# Ethernet_PHY.net
KiCad netlist of a schematic drawn in Altium Designer
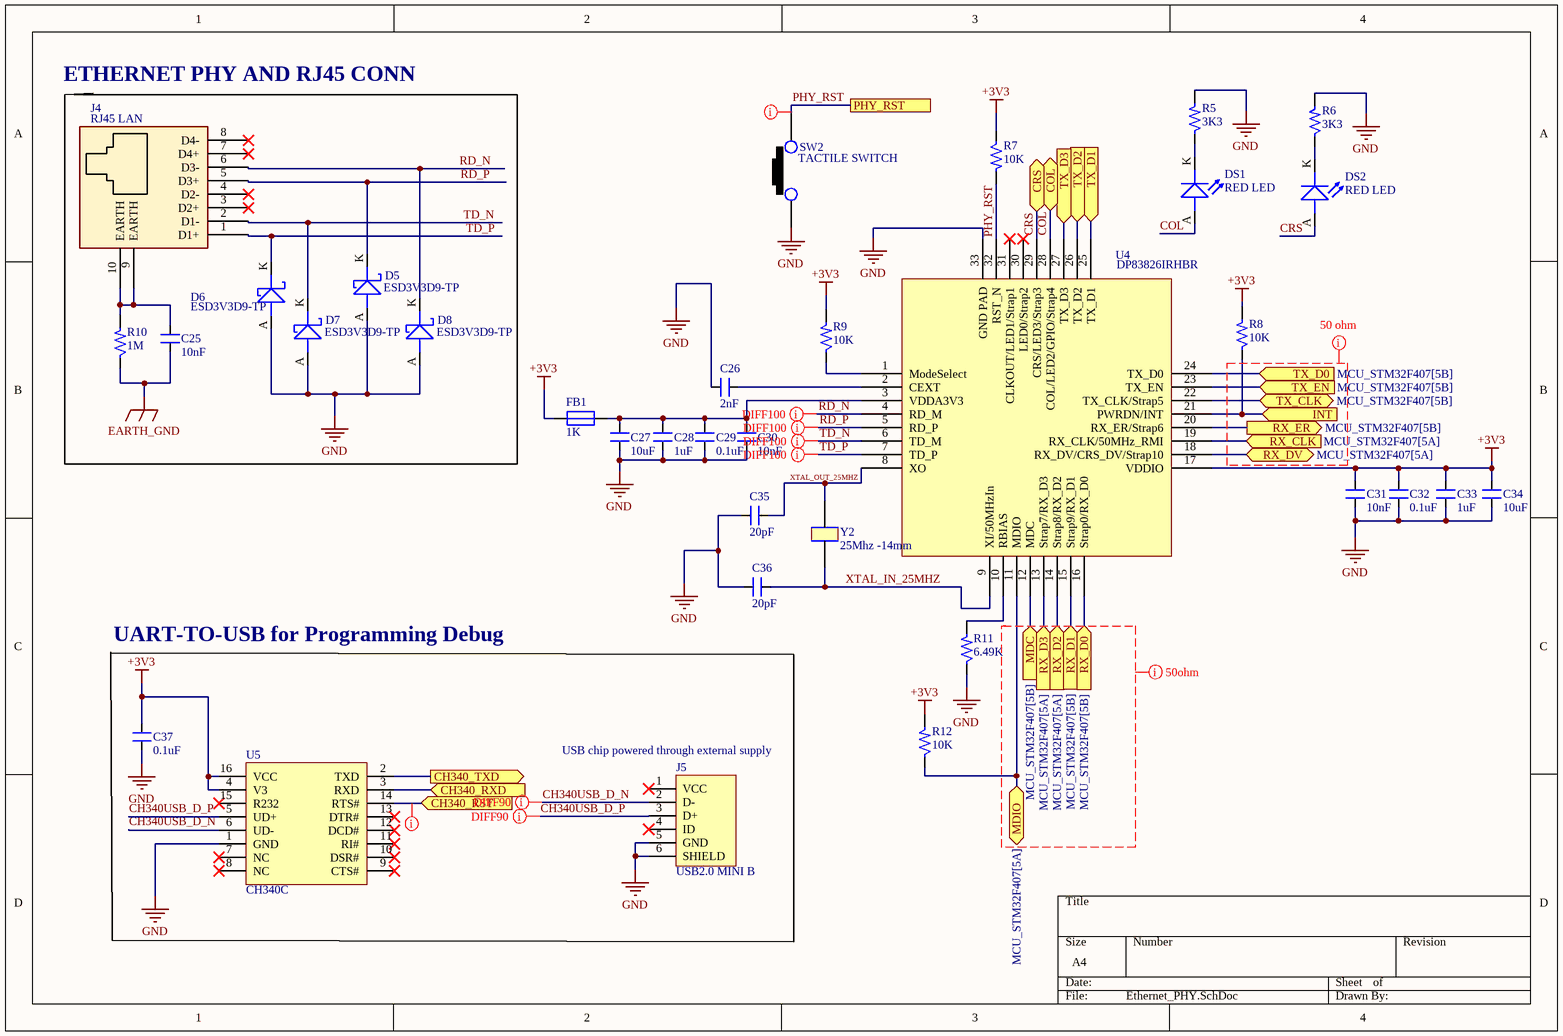
[diagram p0: Ethernet_PHY.SchDoc]

(export (version "E")
  (design (tool "Eeschema 10.0.6"))
  (components
    (comp (ref "C25")
      (value "10nF")
      (footprint "CAP_P196_102X287_H332_RAD_TH")
      (description "10000pF ±10% 1000V (1kV) Ceramic Capacitor X7R Radial")
      (fields
        (field (name "MANUFACTURER") "Yageo")
        (field (name "MANUFACTURER PART NUMBER") "RDER73A103K2K1H03B")
      )
      (libsource (lib "STM32F407_Board") (part "CAP_10nF-1KV-10%-RAD-TH"))
    )
    (comp (ref "C26")
      (value "2nF")
      (footprint "CAP_0805")
      (description "2000pF ±10% 50V Ceramic Capacitor X7R 0805 (2012 Metric)")
      (fields
        (field (name "MANUFACTURER") "Samsung Electro-Mechanics")
        (field (name "MANUFACTURER PART NUMBER") "CL21B202KBANNNC")
      )
      (libsource (lib "STM32F407_Board") (part "CAP_2nF-50V-10%-0805"))
    )
    (comp (ref "C27")
      (value "10uF")
      (footprint "CAP_1206")
      (description "10µF ±10% 50V Ceramic Capacitor X7R 1206 (3216 Metric)")
      (fields
        (field (name "MANUFACTURER") "KEMET")
        (field (name "MANUFACTURER PART NUMBER") "CL31B106KBHNNNE")
      )
      (libsource (lib "STM32F407_Board") (part "CAP_10uF-50V-10%-1206"))
    )
    (comp (ref "C28")
      (value "1uF")
      (footprint "CAP_0805")
      (description "1µF ±5% 50V Ceramic Capacitor X7R 0805 (2012 Metric)")
      (fields
        (field (name "MANUFACTURER") "Samsung")
        (field (name "MANUFACTURER PART NUMBER") "CC0805JKX7R9BB105")
      )
      (libsource (lib "STM32F407_Board") (part "CAP_1uF-50V-5%-0805"))
    )
    (comp (ref "C29")
      (value "0.1uF")
      (footprint "CAP_0805")
      (description "0.1µF ±10% 50V Ceramic Capacitor X7R 0805 (2012 Metric)")
      (fields
        (field (name "MANUFACTURER") "Samsung")
        (field (name "MANUFACTURER PART NUMBER") "CL21B104KBCNNNC")
      )
      (libsource (lib "STM32F407_Board") (part "CAP_0.1uF-50V-10%-0805"))
    )
    (comp (ref "C30")
      (value "10nF")
      (footprint "CAP_0805")
      (description "10000pF ±10% 50V Ceramic Capacitor X7R 0805 (2012 Metric)")
      (fields
        (field (name "MANUFACTURER") "Samsung")
        (field (name "MANUFACTURER PART NUMBER") "C0805C103K5RECAUTO")
      )
      (libsource (lib "STM32F407_Board") (part "CAP_10nF-50V-10%-0805"))
    )
    (comp (ref "C31")
      (value "10nF")
      (footprint "CAP_0805")
      (description "10000pF ±10% 50V Ceramic Capacitor X7R 0805 (2012 Metric)")
      (fields
        (field (name "MANUFACTURER") "Samsung")
        (field (name "MANUFACTURER PART NUMBER") "C0805C103K5RECAUTO")
      )
      (libsource (lib "STM32F407_Board") (part "CAP_10nF-50V-10%-0805"))
    )
    (comp (ref "C32")
      (value "0.1uF")
      (footprint "CAP_0805")
      (description "0.1µF ±10% 50V Ceramic Capacitor X7R 0805 (2012 Metric)")
      (fields
        (field (name "MANUFACTURER") "Samsung")
        (field (name "MANUFACTURER PART NUMBER") "CL21B104KBCNNNC")
      )
      (libsource (lib "STM32F407_Board") (part "CAP_0.1uF-50V-10%-0805"))
    )
    (comp (ref "C33")
      (value "1uF")
      (footprint "CAP_0805")
      (description "1µF ±5% 50V Ceramic Capacitor X7R 0805 (2012 Metric)")
      (fields
        (field (name "MANUFACTURER") "Samsung")
        (field (name "MANUFACTURER PART NUMBER") "CC0805JKX7R9BB105")
      )
      (libsource (lib "STM32F407_Board") (part "CAP_1uF-50V-5%-0805"))
    )
    (comp (ref "C34")
      (value "10uF")
      (footprint "CAP_1206")
      (description "10µF ±10% 50V Ceramic Capacitor X7R 1206 (3216 Metric)")
      (fields
        (field (name "MANUFACTURER") "KEMET")
        (field (name "MANUFACTURER PART NUMBER") "CL31B106KBHNNNE")
      )
      (libsource (lib "STM32F407_Board") (part "CAP_10uF-50V-10%-1206"))
    )
    (comp (ref "C35")
      (value "20pF")
      (footprint "CAP_0805")
      (description "±10% 50V Ceramic Capacitor C0G, NP0 0805 (2012 Metric)")
      (fields
        (field (name "MANUFACTURER") "AVX Corporation")
        (field (name "MANUFACTURER PART NUMBER") "08055A200KAT2A")
      )
      (libsource (lib "STM32F407_Board") (part "CAP_20pF-50V-10%-0805"))
    )
    (comp (ref "C36")
      (value "20pF")
      (footprint "CAP_0805")
      (description "±10% 50V Ceramic Capacitor C0G, NP0 0805 (2012 Metric)")
      (fields
        (field (name "MANUFACTURER") "AVX Corporation")
        (field (name "MANUFACTURER PART NUMBER") "08055A200KAT2A")
      )
      (libsource (lib "STM32F407_Board") (part "CAP_20pF-50V-10%-0805"))
    )
    (comp (ref "C37")
      (value "0.1uF")
      (footprint "CAP_0805")
      (description "0.1µF ±5% 50V Ceramic Capacitor X7R 0805 (2012 Metric)")
      (fields
        (field (name "MANUFACTURER") "AVX Corporation")
        (field (name "MANUFACTURER PART NUMBER") "08055C104JAT4A")
      )
      (libsource (lib "STM32F407_Board") (part "CAP_0.1uF-50V-5%-0805"))
    )
    (comp (ref "D5")
      (value "ESD3V3D9-TP")
      (footprint "DIO_SOD-923")
      (description "8.8V Clamp 5A (8/20µs) Ipp Tvs Diode Surface Mount SOD-923")
      (fields (field (name "MANUFACTURER") "Micro Commercial Co"))
      (libsource (lib "STM32F407_Board") (part "DIO-T_3.3V-8.8V-SOD923"))
    )
    (comp (ref "D6")
      (value "ESD3V3D9-TP")
      (footprint "DIO_SOD-923")
      (description "8.8V Clamp 5A (8/20µs) Ipp Tvs Diode Surface Mount SOD-923")
      (fields (field (name "MANUFACTURER") "Micro Commercial Co"))
      (libsource (lib "STM32F407_Board") (part "DIO-T_3.3V-8.8V-SOD923"))
    )
    (comp (ref "D7")
      (value "ESD3V3D9-TP")
      (footprint "DIO_SOD-923")
      (description "8.8V Clamp 5A (8/20µs) Ipp Tvs Diode Surface Mount SOD-923")
      (fields (field (name "MANUFACTURER") "Micro Commercial Co"))
      (libsource (lib "STM32F407_Board") (part "DIO-T_3.3V-8.8V-SOD923"))
    )
    (comp (ref "D8")
      (value "ESD3V3D9-TP")
      (footprint "DIO_SOD-923")
      (description "8.8V Clamp 5A (8/20µs) Ipp Tvs Diode Surface Mount SOD-923")
      (fields (field (name "MANUFACTURER") "Micro Commercial Co"))
      (libsource (lib "STM32F407_Board") (part "DIO-T_3.3V-8.8V-SOD923"))
    )
    (comp (ref "DS1")
      (value "RED LED")
      (footprint "LED_0805")
      (description "Red 631nm LED Indication - Discrete 2V 0805 (2012 Metric)")
      (fields
        (field (name "MANUFACTURER") "Vishay Lite-On")
        (field (name "MANUFACTURER PART NUMBER") "LTST-C171KRKT")
      )
      (libsource (lib "STM32F407_Board") (part "LED_RED-2V-20mA-0805"))
    )
    (comp (ref "DS2")
      (value "RED LED")
      (footprint "LED_0805")
      (description "Red 631nm LED Indication - Discrete 2V 0805 (2012 Metric)")
      (fields
        (field (name "MANUFACTURER") "Vishay Lite-On")
        (field (name "MANUFACTURER PART NUMBER") "LTST-C171KRKT")
      )
      (libsource (lib "STM32F407_Board") (part "LED_RED-2V-20mA-0805"))
    )
    (comp (ref "FB1")
      (value "1K")
      (footprint "IND_0805")
      (description "1 kOhms @ 100MHz 1 Power Line Ferrite Bead 0805 (2012 Metric) 1.6A")
      (fields
        (field (name "MANUFACTURER") "Laird")
        (field (name "MANUFACTURER PART NUMBER") "BLM21SP102SH1D")
      )
      (libsource (lib "STM32F407_Board") (part "FB_1K-100MHZ-1.6A-0805"))
    )
    (comp (ref "J4")
      (value "RJ45 LAN")
      (footprint "CON10_P106_RJ45_TH_ST")
      (description "8 Pins, 2 Row 2.54mm Pitch, right angle Connector, male")
      (fields
        (field (name "MANUFACTURER") "Assmann")
        (field (name "MANUFACTURER PART NUMBER") "A-2004-2-4-LPS-N-R")
      )
      (libsource (lib "STM32F407_Board") (part "CON-SKT-RJ_8C8P-RA-TH"))
    )
    (comp (ref "J5")
      (value "USB2.0 MINI B")
      (footprint "CON_690-005-299-043")
      (description "USB - mini B USB 2.0 Receptacle Connector 5 Position Surface Mount, Right Angle")
      (fields
        (field (name "MANUFACTURER") "EDAC")
        (field (name "MANUFACTURER PART NUMBER") "690-005-299-043")
      )
      (libsource (lib "STM32F407_Board") (part "CON_USB2.0-MINIB-SMD"))
    )
    (comp (ref "R5")
      (value "3K3")
      (footprint "RES_0603")
      (description "3.3 kOhms ±1% 0.1W, 1/10W Chip Resistor 0603 (1608 Metric) Automotive AEC-Q200 Thick Film")
      (fields (field (name "MANUFACTURER") "Wilson") (field (name "MANUFACTURER PART NUMBER") "WR06X3301FTL"))
      (libsource (lib "STM32F407_Board") (part "RES_3.3K-0.1W-1%-0603"))
    )
    (comp (ref "R6")
      (value "3K3")
      (footprint "RES_0603")
      (description "3.3 kOhms ±1% 0.1W, 1/10W Chip Resistor 0603 (1608 Metric) Automotive AEC-Q200 Thick Film")
      (fields (field (name "MANUFACTURER") "Wilson") (field (name "MANUFACTURER PART NUMBER") "WR06X3301FTL"))
      (libsource (lib "STM32F407_Board") (part "RES_3.3K-0.1W-1%-0603"))
    )
    (comp (ref "R7")
      (value "10K")
      (footprint "RES_0603")
      (description "10 kOhms ±1% 0.1W, 1/10W Chip Resistor 0603 (1608 Metric) Automotive AEC-Q200 Thick Film")
      (fields (field (name "MANUFACTURER") "Walsin") (field (name "MANUFACTURER PART NUMBER") "WR06X1002FTL"))
      (libsource (lib "STM32F407_Board") (part "RES_10K-0.1W-1%-0603"))
    )
    (comp (ref "R8")
      (value "10K")
      (footprint "RES_0603")
      (description "10 kOhms ±1% 0.1W, 1/10W Chip Resistor 0603 (1608 Metric) Automotive AEC-Q200 Thick Film")
      (fields (field (name "MANUFACTURER") "Walsin") (field (name "MANUFACTURER PART NUMBER") "WR06X1002FTL"))
      (libsource (lib "STM32F407_Board") (part "RES_10K-0.1W-1%-0603"))
    )
    (comp (ref "R9")
      (value "10K")
      (footprint "RES_0603")
      (description "10 kOhms ±1% 0.1W, 1/10W Chip Resistor 0603 (1608 Metric) Automotive AEC-Q200 Thick Film")
      (fields (field (name "MANUFACTURER") "Walsin") (field (name "MANUFACTURER PART NUMBER") "WR06X1002FTL"))
      (libsource (lib "STM32F407_Board") (part "RES_10K-0.1W-1%-0603"))
    )
    (comp (ref "R10")
      (value "1M")
      (footprint "RES_1206")
      (fields (field (name "MANUFACTURER") "Walsin") (field (name "MANUFACTURER PART NUMBER") "WR12X1004FTL"))
      (libsource (lib "STM32F407_Board") (part "RES_1M-0.25W-1%-1206"))
    )
    (comp (ref "R11")
      (value "6.49K")
      (footprint "RES_0805")
      (description "6.49 kOhms ±1% 0.125W, 1/8W Chip Resistor 0805 (2012 Metric) Moisture Resistant Thick Film")
      (fields
        (field (name "MANUFACTURER") "Stackpole Electronics")
        (field (name "MANUFACTURER PART NUMBER") "RC0805FR-076K49L")
      )
      (libsource (lib "STM32F407_Board") (part "RES_6.49K-0.125W-1%-0805"))
    )
    (comp (ref "R12")
      (value "10K")
      (footprint "RES_0603")
      (description "10 kOhms ±1% 0.1W, 1/10W Chip Resistor 0603 (1608 Metric) Automotive AEC-Q200 Thick Film")
      (fields (field (name "MANUFACTURER") "Walsin") (field (name "MANUFACTURER PART NUMBER") "WR06X1002FTL"))
      (libsource (lib "STM32F407_Board") (part "RES_10K-0.1W-1%-0603"))
    )
    (comp (ref "SW2")
      (value "TACTILE SWITCH")
      (footprint "SW_342_SMD")
      (description "Tactile Switch SPST-NO Top Actuated Surface Mount")
      (fields
        (field (name "MANUFACTURER") "ITT C&K")
        (field (name "MANUFACTURER PART NUMBER") "RS-282G05A3-SMRT")
      )
      (libsource (lib "STM32F407_Board") (part "SW1_RS-282G05A3-SMRT-SMD"))
    )
    (comp (ref "U4")
      (value "DP83826IRHBR")
      (footprint "VQFN32_19_218_23X9_SMD")
      (fields (field (name "MANUFACTURER") "Texas Instruments"))
      (libsource (lib "STM32F407_Board") (part "IC_DP83826IRHBR"))
    )
    (comp (ref "U5")
      (value "CH340C")
      (footprint "SOIC16_50_284_25X90_SMT")
      (description "USB Bridge, USB to UART USB 2.0 UART Interface")
      (fields (field (name "MANUFACTURER") "Olimex"))
      (libsource (lib "STM32F407_Board") (part "IC_CH340C"))
    )
    (comp (ref "Y2")
      (value "25Mhz -14mm")
      (footprint "XTAL_314_240X47_SMD")
      (description "25MHz ±30ppm Crystal 20pF 30 Ohms HC-49/US")
      (fields
        (field (name "MANUFACTURER") "Abracon")
        (field (name "MANUFACTURER PART NUMBER") "FOXSDLF/250F-20")
      )
      (libsource (lib "STM32F407_Board") (part "XTAL_25Mhz-FOXSDLF/250F-20"))
    )
  )
  (nets
    (net (code "1") (name "+3V3") (class "Default")
      (node (ref "C31") (pin "2") (pinfunction "2_2") (pintype "passive"))
      (node (ref "C32") (pin "2") (pinfunction "2_2") (pintype "passive"))
      (node (ref "C33") (pin "2") (pinfunction "2_2") (pintype "passive"))
      (node (ref "C34") (pin "2") (pinfunction "2_2") (pintype "passive"))
      (node (ref "C37") (pin "2") (pinfunction "2_2") (pintype "passive"))
      (node (ref "FB1") (pin "1") (pinfunction "1_1") (pintype "passive"))
      (node (ref "R12") (pin "2") (pinfunction "2_2") (pintype "passive"))
      (node (ref "R7") (pin "1") (pinfunction "1_1") (pintype "passive"))
      (node (ref "R8") (pin "2") (pinfunction "2_2") (pintype "passive"))
      (node (ref "R9") (pin "2") (pinfunction "2_2") (pintype "passive"))
      (node (ref "U4") (pin "17") (pinfunction "VDDIO_17") (pintype "passive"))
      (node (ref "U5") (pin "16") (pinfunction "VCC_16") (pintype "passive"))
      (node (ref "U5") (pin "4") (pinfunction "V3_4") (pintype "passive"))
    )
    (net (code "2") (name "/CH340USB_D_N") (class "Default")
      (node (ref "J5") (pin "2") (pinfunction "D-_2") (pintype "passive"))
      (node (ref "U5") (pin "6") (pinfunction "UD-_6") (pintype "passive"))
    )
    (net (code "3") (name "/CH340USB_D_P") (class "Default")
      (node (ref "J5") (pin "3") (pinfunction "D+_3") (pintype "passive"))
      (node (ref "U5") (pin "5") (pinfunction "UD+_5") (pintype "passive"))
    )
    (net (code "4") (name "/CH340_RST") (class "Default")
      (node (ref "U5") (pin "14") (pinfunction "RTS#_14") (pintype "passive"))
    )
    (net (code "5") (name "/CH340_RXD") (class "Default")
      (node (ref "U5") (pin "3") (pinfunction "RXD_3") (pintype "passive"))
    )
    (net (code "6") (name "/CH340_TXD") (class "Default")
      (node (ref "U5") (pin "2") (pinfunction "TXD_2") (pintype "passive"))
    )
    (net (code "7") (name "/COL") (class "Default")
      (node (ref "DS1") (pin "A") (pinfunction "ANODE_A") (pintype "passive"))
      (node (ref "U4") (pin "28") (pinfunction "COL/LED2/GPIO/Strap4_28") (pintype "passive"))
    )
    (net (code "8") (name "/CRS") (class "Default")
      (node (ref "DS2") (pin "A") (pinfunction "ANODE_A") (pintype "passive"))
      (node (ref "U4") (pin "29") (pinfunction "CRS/LED3/Strap3_29") (pintype "passive"))
    )
    (net (code "9") (name "/INT") (class "Default")
      (node (ref "R8") (pin "1") (pinfunction "1_1") (pintype "passive"))
      (node (ref "U4") (pin "21") (pinfunction "PWRDN/INT_21") (pintype "passive"))
    )
    (net (code "10") (name "/MDC") (class "Default")
      (node (ref "U4") (pin "12") (pinfunction "MDC_12") (pintype "passive"))
    )
    (net (code "11") (name "/MDIO") (class "Default")
      (node (ref "R12") (pin "1") (pinfunction "1_1") (pintype "passive"))
      (node (ref "U4") (pin "11") (pinfunction "MDIO_11") (pintype "passive"))
    )
    (net (code "12") (name "/PHY_RST") (class "Default")
      (node (ref "R7") (pin "2") (pinfunction "2_2") (pintype "passive"))
      (node (ref "SW2") (pin "2") (pinfunction "2_2") (pintype "passive"))
      (node (ref "U4") (pin "32") (pinfunction "RST_N_32") (pintype "passive"))
    )
    (net (code "13") (name "/RD_N") (class "Default")
      (node (ref "D8") (pin "K") (pinfunction "K_K") (pintype "passive"))
      (node (ref "J4") (pin "6") (pinfunction "D3-_6") (pintype "passive"))
      (node (ref "U4") (pin "4") (pinfunction "RD_M_4") (pintype "passive"))
    )
    (net (code "14") (name "/RD_P") (class "Default")
      (node (ref "D5") (pin "K") (pinfunction "K_K") (pintype "passive"))
      (node (ref "J4") (pin "5") (pinfunction "D3+_5") (pintype "passive"))
      (node (ref "U4") (pin "5") (pinfunction "RD_P_5") (pintype "passive"))
    )
    (net (code "15") (name "/RX_CLK") (class "Default")
      (node (ref "U4") (pin "19") (pinfunction "RX_CLK/50MHz_RMI_19") (pintype "passive"))
    )
    (net (code "16") (name "/RX_D0") (class "Default")
      (node (ref "U4") (pin "16") (pinfunction "Strap0/RX_D0_16") (pintype "passive"))
    )
    (net (code "17") (name "/RX_D1") (class "Default")
      (node (ref "U4") (pin "15") (pinfunction "Strap9/RX_D1_15") (pintype "passive"))
    )
    (net (code "18") (name "/RX_D2") (class "Default")
      (node (ref "U4") (pin "14") (pinfunction "Strap8/RX_D2_14") (pintype "passive"))
    )
    (net (code "19") (name "/RX_D3") (class "Default")
      (node (ref "U4") (pin "13") (pinfunction "Strap7/RX_D3_13") (pintype "passive"))
    )
    (net (code "20") (name "/RX_DV") (class "Default")
      (node (ref "U4") (pin "18") (pinfunction "RX_DV/CRS_DV/Strap10_18") (pintype "passive"))
    )
    (net (code "21") (name "/RX_ER") (class "Default")
      (node (ref "U4") (pin "20") (pinfunction "RX_ER/Strap6_20") (pintype "passive"))
    )
    (net (code "22") (name "/TD_N") (class "Default")
      (node (ref "D7") (pin "K") (pinfunction "K_K") (pintype "passive"))
      (node (ref "J4") (pin "2") (pinfunction "D1-_2") (pintype "passive"))
      (node (ref "U4") (pin "6") (pinfunction "TD_M_6") (pintype "passive"))
    )
    (net (code "23") (name "/TD_P") (class "Default")
      (node (ref "D6") (pin "K") (pinfunction "K_K") (pintype "passive"))
      (node (ref "J4") (pin "1") (pinfunction "D1+_1") (pintype "passive"))
      (node (ref "U4") (pin "7") (pinfunction "TD_P_7") (pintype "passive"))
    )
    (net (code "24") (name "/TX_CLK") (class "Default")
      (node (ref "U4") (pin "22") (pinfunction "TX_CLK/Strap5_22") (pintype "passive"))
    )
    (net (code "25") (name "/TX_D0") (class "Default")
      (node (ref "U4") (pin "24") (pinfunction "TX_D0_24") (pintype "passive"))
    )
    (net (code "26") (name "/TX_D1") (class "Default")
      (node (ref "U4") (pin "25") (pinfunction "TX_D1_25") (pintype "passive"))
    )
    (net (code "27") (name "/TX_D2") (class "Default")
      (node (ref "U4") (pin "26") (pinfunction "TX_D2_26") (pintype "passive"))
    )
    (net (code "28") (name "/TX_D3") (class "Default")
      (node (ref "U4") (pin "27") (pinfunction "TX_D3_27") (pintype "passive"))
    )
    (net (code "29") (name "/TX_EN") (class "Default")
      (node (ref "U4") (pin "23") (pinfunction "TX_EN_23") (pintype "passive"))
    )
    (net (code "30") (name "/XTAL_IN_25MHZ") (class "Default")
      (node (ref "C36") (pin "2") (pinfunction "2_2") (pintype "passive"))
      (node (ref "U4") (pin "9") (pinfunction "XI/50MHzIn_9") (pintype "passive"))
      (node (ref "Y2") (pin "2") (pinfunction "2_2") (pintype "passive"))
    )
    (net (code "31") (name "/XTAL_OUT_25MHZ") (class "Default")
      (node (ref "C35") (pin "2") (pinfunction "2_2") (pintype "passive"))
      (node (ref "U4") (pin "8") (pinfunction "XO_8") (pintype "passive"))
      (node (ref "Y2") (pin "1") (pinfunction "1_1") (pintype "passive"))
    )
    (net (code "32") (name "EARTH_GND") (class "Default")
      (node (ref "C25") (pin "1") (pinfunction "1_1") (pintype "passive"))
      (node (ref "R10") (pin "1") (pinfunction "1_1") (pintype "passive"))
    )
    (net (code "33") (name "GND") (class "Default")
      (node (ref "C26") (pin "2") (pinfunction "2_2") (pintype "passive"))
      (node (ref "C27") (pin "1") (pinfunction "1_1") (pintype "passive"))
      (node (ref "C28") (pin "1") (pinfunction "1_1") (pintype "passive"))
      (node (ref "C29") (pin "1") (pinfunction "1_1") (pintype "passive"))
      (node (ref "C30") (pin "1") (pinfunction "1_1") (pintype "passive"))
      (node (ref "C31") (pin "1") (pinfunction "1_1") (pintype "passive"))
      (node (ref "C32") (pin "1") (pinfunction "1_1") (pintype "passive"))
      (node (ref "C33") (pin "1") (pinfunction "1_1") (pintype "passive"))
      (node (ref "C34") (pin "1") (pinfunction "1_1") (pintype "passive"))
      (node (ref "C35") (pin "1") (pinfunction "1_1") (pintype "passive"))
      (node (ref "C36") (pin "1") (pinfunction "1_1") (pintype "passive"))
      (node (ref "C37") (pin "1") (pinfunction "1_1") (pintype "passive"))
      (node (ref "D5") (pin "A") (pinfunction "A_A") (pintype "passive"))
      (node (ref "D6") (pin "A") (pinfunction "A_A") (pintype "passive"))
      (node (ref "D7") (pin "A") (pinfunction "A_A") (pintype "passive"))
      (node (ref "D8") (pin "A") (pinfunction "A_A") (pintype "passive"))
      (node (ref "J5") (pin "5") (pinfunction "GND_5") (pintype "passive"))
      (node (ref "J5") (pin "6") (pinfunction "SHIELD_6") (pintype "passive"))
      (node (ref "R11") (pin "1") (pinfunction "1_1") (pintype "passive"))
      (node (ref "R5") (pin "2") (pinfunction "2_2") (pintype "passive"))
      (node (ref "R6") (pin "2") (pinfunction "2_2") (pintype "passive"))
      (node (ref "SW2") (pin "1") (pinfunction "1_1") (pintype "passive"))
      (node (ref "U4") (pin "33") (pinfunction "GND_PAD_33") (pintype "passive"))
      (node (ref "U5") (pin "1") (pinfunction "GND_1") (pintype "passive"))
    )
    (net (code "34") (name "Net-(C25-Pad2)") (class "Default")
      (node (ref "C25") (pin "2") (pinfunction "2_2") (pintype "passive"))
      (node (ref "J4") (pin "10") (pinfunction "EARTH_10") (pintype "passive"))
      (node (ref "J4") (pin "9") (pinfunction "EARTH_9") (pintype "passive"))
      (node (ref "R10") (pin "2") (pinfunction "2_2") (pintype "passive"))
    )
    (net (code "35") (name "Net-(DS1-CATHODE)") (class "Default")
      (node (ref "DS1") (pin "K") (pinfunction "CATHODE_K") (pintype "passive"))
      (node (ref "R5") (pin "1") (pinfunction "1_1") (pintype "passive"))
    )
    (net (code "36") (name "Net-(DS2-CATHODE)") (class "Default")
      (node (ref "DS2") (pin "K") (pinfunction "CATHODE_K") (pintype "passive"))
      (node (ref "R6") (pin "1") (pinfunction "1_1") (pintype "passive"))
    )
    (net (code "37") (name "Net-(U4-CEXT)") (class "Default")
      (node (ref "C26") (pin "1") (pinfunction "1_1") (pintype "passive"))
      (node (ref "U4") (pin "2") (pinfunction "CEXT_2") (pintype "passive"))
    )
    (net (code "38") (name "Net-(U4-ModeSelect)") (class "Default")
      (node (ref "R9") (pin "1") (pinfunction "1_1") (pintype "passive"))
      (node (ref "U4") (pin "1") (pinfunction "ModeSelect_1") (pintype "passive"))
    )
    (net (code "39") (name "Net-(U4-RBIAS)") (class "Default")
      (node (ref "R11") (pin "2") (pinfunction "2_2") (pintype "passive"))
      (node (ref "U4") (pin "10") (pinfunction "RBIAS_10") (pintype "passive"))
    )
    (net (code "40") (name "Net-(U4-VDDA3V3)") (class "Default")
      (node (ref "C27") (pin "2") (pinfunction "2_2") (pintype "passive"))
      (node (ref "C28") (pin "2") (pinfunction "2_2") (pintype "passive"))
      (node (ref "C29") (pin "2") (pinfunction "2_2") (pintype "passive"))
      (node (ref "C30") (pin "2") (pinfunction "2_2") (pintype "passive"))
      (node (ref "FB1") (pin "2") (pinfunction "2_2") (pintype "passive"))
      (node (ref "U4") (pin "3") (pinfunction "VDDA3V3_3") (pintype "passive"))
    )
    (net (code "41") (name "unconnected-(J4-D2+-Pad3)") (class "Default")
      (node (ref "J4") (pin "3") (pinfunction "D2+_3") (pintype "passive+no_connect"))
    )
    (net (code "42") (name "unconnected-(J4-D2--Pad4)") (class "Default")
      (node (ref "J4") (pin "4") (pinfunction "D2-_4") (pintype "passive+no_connect"))
    )
    (net (code "43") (name "unconnected-(J4-D4+-Pad7)") (class "Default")
      (node (ref "J4") (pin "7") (pinfunction "D4+_7") (pintype "passive+no_connect"))
    )
    (net (code "44") (name "unconnected-(J4-D4--Pad8)") (class "Default")
      (node (ref "J4") (pin "8") (pinfunction "D4-_8") (pintype "passive+no_connect"))
    )
    (net (code "45") (name "unconnected-(J5-ID-Pad4)") (class "Default")
      (node (ref "J5") (pin "4") (pinfunction "ID_4") (pintype "passive+no_connect"))
    )
    (net (code "46") (name "unconnected-(J5-VCC-Pad1)") (class "Default")
      (node (ref "J5") (pin "1") (pinfunction "VCC_1") (pintype "passive+no_connect"))
    )
    (net (code "47") (name "unconnected-(U4-CLKOUT{slash}LED1{slash}Strap1-Pad31)") (class "Default")
      (node (ref "U4") (pin "31") (pinfunction "CLKOUT/LED1/Strap1_31") (pintype "passive+no_connect"))
    )
    (net (code "48") (name "unconnected-(U4-LED0{slash}Strap2-Pad30)") (class "Default")
      (node (ref "U4") (pin "30") (pinfunction "LED0/Strap2_30") (pintype "passive+no_connect"))
    )
    (net (code "49") (name "unconnected-(U5-CTS#-Pad9)") (class "Default")
      (node (ref "U5") (pin "9") (pinfunction "CTS#_9") (pintype "passive+no_connect"))
    )
    (net (code "50") (name "unconnected-(U5-DCD#-Pad12)") (class "Default")
      (node (ref "U5") (pin "12") (pinfunction "DCD#_12") (pintype "passive+no_connect"))
    )
    (net (code "51") (name "unconnected-(U5-DSR#-Pad10)") (class "Default")
      (node (ref "U5") (pin "10") (pinfunction "DSR#_10") (pintype "passive+no_connect"))
    )
    (net (code "52") (name "unconnected-(U5-DTR#-Pad13)") (class "Default")
      (node (ref "U5") (pin "13") (pinfunction "DTR#_13") (pintype "passive+no_connect"))
    )
    (net (code "53") (name "unconnected-(U5-NC-Pad7)") (class "Default")
      (node (ref "U5") (pin "7") (pinfunction "NC_7") (pintype "passive+no_connect"))
    )
    (net (code "54") (name "unconnected-(U5-NC-Pad8)") (class "Default")
      (node (ref "U5") (pin "8") (pinfunction "NC_8") (pintype "passive+no_connect"))
    )
    (net (code "55") (name "unconnected-(U5-R232-Pad15)") (class "Default")
      (node (ref "U5") (pin "15") (pinfunction "R232_15") (pintype "passive+no_connect"))
    )
    (net (code "56") (name "unconnected-(U5-RI#-Pad11)") (class "Default")
      (node (ref "U5") (pin "11") (pinfunction "RI#_11") (pintype "passive+no_connect"))
    )
  )
)
